# design.net
KiCad netlist of a schematic drawn in Altium Designer
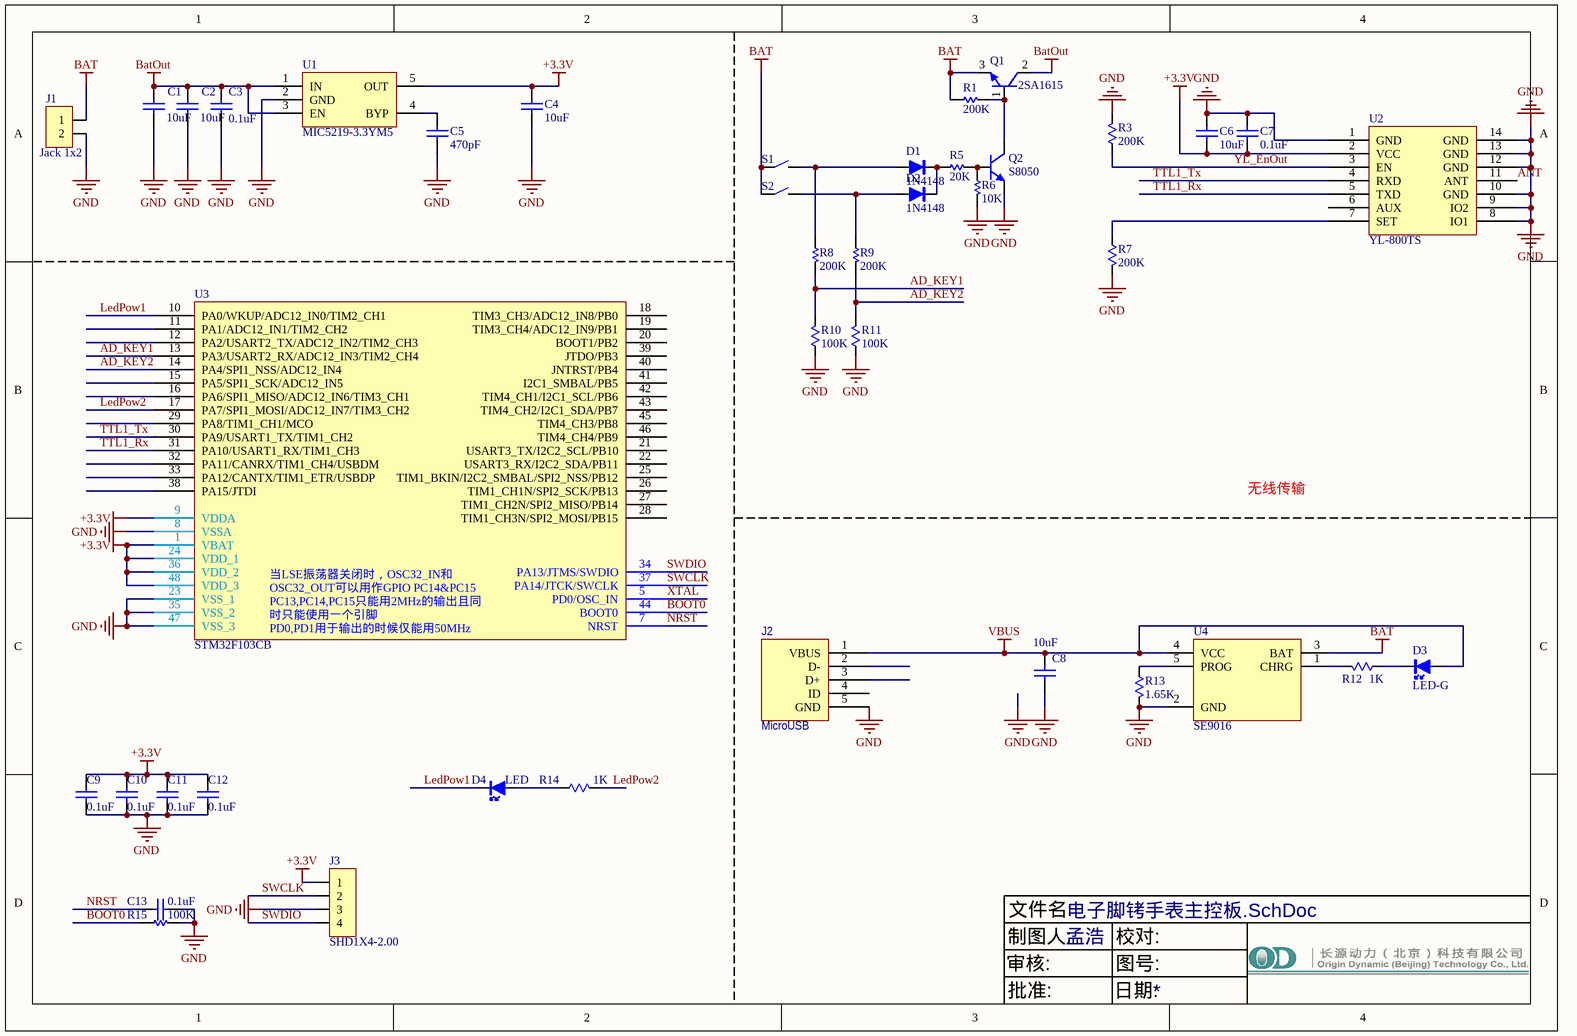
[diagram p0: 电子脚铐手表主控板.SchDoc]

(export (version "E")
  (design (tool "Eeschema 10.0.6"))
  (components
    (comp (ref "C1")
      (value "10uF")
      (footprint "C0603")
      (description "CAP")
      (fields (field (name "PUBLISHER") "Altium Limited"))
      (libsource (lib "Passive Components Class") (part "CAP"))
    )
    (comp (ref "C2")
      (value "10uF")
      (footprint "C0603")
      (description "CAP")
      (fields (field (name "PUBLISHER") "Altium Limited"))
      (libsource (lib "Passive Components Class") (part "CAP"))
    )
    (comp (ref "C3") (value "0.1uF") (footprint "C0603") (libsource (lib "RLCYDF") (part "Cap Semi")))
    (comp (ref "C4")
      (value "10uF")
      (footprint "C0603")
      (description "CAP")
      (fields (field (name "PUBLISHER") "Altium Limited"))
      (libsource (lib "Passive Components Class") (part "CAP"))
    )
    (comp (ref "C5")
      (value "470pF")
      (footprint "C0603")
      (description "CAP")
      (fields (field (name "PUBLISHER") "Altium Limited"))
      (libsource (lib "Passive Components Class") (part "CAP"))
    )
    (comp (ref "C6")
      (value "10uF")
      (footprint "C0603")
      (description "CAP")
      (fields (field (name "PUBLISHER") "Altium Limited"))
      (libsource (lib "Passive Components Class") (part "CAP"))
    )
    (comp (ref "C7")
      (value "0.1uF")
      (footprint "C0603")
      (description "CAP")
      (fields (field (name "PUBLISHER") "Altium Limited"))
      (libsource (lib "Passive Components Class") (part "CAP"))
    )
    (comp (ref "C8")
      (value "10uF")
      (footprint "C0603")
      (description "Capacitor")
      (fields (field (name "PUBLISHER") "Altium Limited"))
      (libsource (lib "Miscellaneous Devices") (part "Cap"))
    )
    (comp (ref "C9") (value "0.1uF") (footprint "C0603") (libsource (lib "RLCYDF") (part "Cap Semi")))
    (comp (ref "C10") (value "0.1uF") (footprint "C0603") (libsource (lib "RLCYDF") (part "Cap Semi")))
    (comp (ref "C11") (value "0.1uF") (footprint "C0603") (libsource (lib "RLCYDF") (part "Cap Semi")))
    (comp (ref "C12") (value "0.1uF") (footprint "C0603") (libsource (lib "RLCYDF") (part "Cap Semi")))
    (comp (ref "C13") (value "0.1uF") (footprint "C0603") (libsource (lib "RLCYDF") (part "Cap Semi")))
    (comp (ref "D1")
      (value "1N4148")
      (footprint "SOD-80-S")
      (description "Silicon Epitaxial Planar Diodes")
      (libsource (lib "Passive Components Class") (part "DIODE-SWITCHING"))
    )
    (comp (ref "D2")
      (value "1N4148")
      (footprint "SOD-80-S")
      (description "Silicon Epitaxial Planar Diodes")
      (libsource (lib "Passive Components Class") (part "DIODE-SWITCHING"))
    )
    (comp (ref "D3")
      (value "LED-G")
      (footprint "LED0603")
      (libsource (lib "Passive Components Class") (part "LED"))
    )
    (comp (ref "D4")
      (value "LED")
      (footprint "Led1206")
      (libsource (lib "Passive Components Class") (part "LED"))
    )
    (comp (ref "J1")
      (value "Jack 1x2")
      (footprint "Jk1*2-2.0")
      (description "插座")
      (libsource (lib "Connector") (part "Jack 1x2"))
    )
    (comp (ref "J2") (value "MicroUSB") (footprint "MICRO-USB") (libsource (lib "JLib") (part "MicroUSB")))
    (comp (ref "J3")
      (value "SHD1X4-2.00")
      (footprint "Jk1*4-2.0")
      (libsource (lib "Connector Class") (part "HEADER1X4"))
    )
    (comp (ref "Q1") (value "2SA1615") (footprint "TO-252") (libsource (lib "ArmArmor") (part "MJD122")))
    (comp (ref "Q2")
      (value "S8050")
      (footprint "SOT-23")
      (description "NPN triode, 0.5A Max")
      (libsource (lib "RLCYDF") (part "S8050"))
    )
    (comp (ref "R1") (value "200K") (footprint "R0603") (libsource (lib "RLCYDF") (part "Res")))
    (comp (ref "R3")
      (value "200K")
      (footprint "R0603")
      (description "Resistor")
      (fields (field (name "PUBLISHER") "Altium Limited"))
      (libsource (lib "Passive Components Class") (part "RES"))
    )
    (comp (ref "R5") (value "20K") (footprint "R0603") (libsource (lib "RLCYDF") (part "Res")))
    (comp (ref "R6") (value "10K") (footprint "R0603") (libsource (lib "RLCYDF") (part "Res")))
    (comp (ref "R7")
      (value "200K")
      (footprint "R0603")
      (description "Resistor")
      (fields (field (name "PUBLISHER") "Altium Limited"))
      (libsource (lib "Passive Components Class") (part "RES"))
    )
    (comp (ref "R8") (value "200K") (footprint "R0603") (libsource (lib "RLCYDF") (part "Res")))
    (comp (ref "R9") (value "200K") (footprint "R0603") (libsource (lib "RLCYDF") (part "Res")))
    (comp (ref "R10")
      (value "100K")
      (footprint "R0603")
      (description "Resistor")
      (fields (field (name "PUBLISHER") "Altium Limited"))
      (libsource (lib "Passive Components Class") (part "RES"))
    )
    (comp (ref "R11")
      (value "100K")
      (footprint "R0603")
      (description "Resistor")
      (fields (field (name "PUBLISHER") "Altium Limited"))
      (libsource (lib "Passive Components Class") (part "RES"))
    )
    (comp (ref "R12")
      (value "1K")
      (footprint "R0603")
      (description "Resistor")
      (fields (field (name "PUBLISHER") "Altium Limited"))
      (libsource (lib "UP-Robot") (part "Res"))
    )
    (comp (ref "R13")
      (value "1.65K")
      (footprint "R0603")
      (description "Resistor")
      (fields (field (name "PUBLISHER") "Altium Limited"))
      (libsource (lib "Temp") (part "Res"))
    )
    (comp (ref "R14")
      (value "1K")
      (footprint "R0603")
      (description "Resistor")
      (fields (field (name "PUBLISHER") "Altium Limited"))
      (libsource (lib "UP-Robot") (part "Res"))
    )
    (comp (ref "R15") (value "100K") (footprint "R0603") (libsource (lib "RLCYDF") (part "Res")))
    (comp (ref "S1") (value "Switch") (footprint "TS-1110U") (libsource (lib "Connector") (part "Sw")))
    (comp (ref "S2") (value "Switch") (footprint "SIDE_BUTTON") (libsource (lib "Connector") (part "Sw")))
    (comp (ref "U1")
      (value "MIC5219-3.3YM5")
      (footprint "SOT-23-5")
      (libsource (lib "Power") (part "MIC5205"))
    )
    (comp (ref "U2") (value "YL-800TS") (footprint "YL-800TS") (libsource (lib "Module") (part "YL-800TS")))
    (comp (ref "U3")
      (value "STM32F103CB")
      (footprint "LQFP48")
      (libsource (lib "stm32") (part "STM32F103Cx"))
    )
    (comp (ref "U4") (value "SE9016") (footprint "SOT-23-5") (libsource (lib "chip") (part "SE9016")))
  )
  (nets
    (net (code "1") (name "+3.3V") (class "Default")
      (node (ref "C10") (pin "1") (pinfunction "1_1") (pintype "passive"))
      (node (ref "C11") (pin "1") (pinfunction "1_1") (pintype "passive"))
      (node (ref "C12") (pin "1") (pinfunction "1_1") (pintype "passive"))
      (node (ref "C4") (pin "1") (pinfunction "1_1") (pintype "passive"))
      (node (ref "C6") (pin "1") (pinfunction "1_1") (pintype "passive"))
      (node (ref "C7") (pin "1") (pinfunction "1_1") (pintype "passive"))
      (node (ref "C9") (pin "1") (pinfunction "1_1") (pintype "passive"))
      (node (ref "J3") (pin "1") (pinfunction "1_1") (pintype "passive"))
      (node (ref "U1") (pin "5") (pinfunction "OUT_5") (pintype "passive"))
      (node (ref "U2") (pin "2") (pinfunction "VCC_2") (pintype "passive"))
      (node (ref "U3") (pin "1") (pinfunction "VBAT_1") (pintype "power_in"))
      (node (ref "U3") (pin "24") (pinfunction "VDD_1_24") (pintype "power_in"))
      (node (ref "U3") (pin "36") (pinfunction "VDD_2_36") (pintype "power_in"))
      (node (ref "U3") (pin "48") (pinfunction "VDD_3_48") (pintype "power_in"))
      (node (ref "U3") (pin "9") (pinfunction "VDDA_9") (pintype "power_in"))
    )
    (net (code "2") (name "/AD_KEY1") (class "Default")
      (node (ref "R10") (pin "2") (pinfunction "2_2") (pintype "passive"))
      (node (ref "R8") (pin "2") (pinfunction "2_2") (pintype "passive"))
      (node (ref "U3") (pin "13") (pinfunction "PA3/USART2_RX/ADC12_IN3/TIM2_CH4_13") (pintype "passive"))
    )
    (net (code "3") (name "/AD_KEY2") (class "Default")
      (node (ref "R11") (pin "2") (pinfunction "2_2") (pintype "passive"))
      (node (ref "R9") (pin "2") (pinfunction "2_2") (pintype "passive"))
      (node (ref "U3") (pin "14") (pinfunction "PA4/SPI1_NSS/ADC12_IN4_14") (pintype "passive"))
    )
    (net (code "4") (name "/ANT") (class "Default")
      (node (ref "U2") (pin "11") (pinfunction "ANT_11") (pintype "passive"))
    )
    (net (code "5") (name "/BOOT0") (class "Default")
      (node (ref "R15") (pin "1") (pinfunction "1_1") (pintype "passive"))
      (node (ref "U3") (pin "44") (pinfunction "BOOT0_44") (pintype "passive"))
    )
    (net (code "6") (name "/LedPow1") (class "Default")
      (node (ref "D4") (pin "2") (pinfunction "K_2") (pintype "passive"))
      (node (ref "U3") (pin "10") (pinfunction "PA0/WKUP/ADC12_IN0/TIM2_CH1_10") (pintype "passive"))
    )
    (net (code "7") (name "/LedPow2") (class "Default")
      (node (ref "R14") (pin "1") (pinfunction "1_1") (pintype "passive"))
      (node (ref "U3") (pin "17") (pinfunction "PA7/SPI1_MOSI/ADC12_IN7/TIM3_CH2_17") (pintype "passive"))
    )
    (net (code "8") (name "/NRST") (class "Default")
      (node (ref "C13") (pin "1") (pinfunction "1_1") (pintype "passive"))
      (node (ref "U3") (pin "7") (pinfunction "NRST_7") (pintype "passive"))
    )
    (net (code "9") (name "/SWCLK") (class "Default")
      (node (ref "J3") (pin "2") (pinfunction "2_2") (pintype "passive"))
      (node (ref "U3") (pin "37") (pinfunction "PA14/JTCK/SWCLK_37") (pintype "passive"))
    )
    (net (code "10") (name "/SWDIO") (class "Default")
      (node (ref "J3") (pin "4") (pinfunction "4_4") (pintype "passive"))
      (node (ref "U3") (pin "34") (pinfunction "PA13/JTMS/SWDIO_34") (pintype "passive"))
    )
    (net (code "11") (name "/TTL1_Rx") (class "Default")
      (node (ref "U2") (pin "5") (pinfunction "TXD_5") (pintype "passive"))
      (node (ref "U3") (pin "31") (pinfunction "PA10/USART1_RX/TIM1_CH3_31") (pintype "passive"))
    )
    (net (code "12") (name "/TTL1_Tx") (class "Default")
      (node (ref "U2") (pin "4") (pinfunction "RXD_4") (pintype "passive"))
      (node (ref "U3") (pin "30") (pinfunction "PA9/USART1_TX/TIM1_CH2_30") (pintype "passive"))
    )
    (net (code "13") (name "/XTAL") (class "Default")
      (node (ref "U3") (pin "5") (pinfunction "PD0/OSC_IN_5") (pintype "passive"))
    )
    (net (code "14") (name "/YL_EnOut") (class "Default")
      (node (ref "R3") (pin "1") (pinfunction "1_1") (pintype "passive"))
      (node (ref "U2") (pin "3") (pinfunction "EN_3") (pintype "passive"))
    )
    (net (code "15") (name "BAT") (class "Default")
      (node (ref "J1") (pin "1") (pinfunction "1_1") (pintype "passive"))
      (node (ref "Q1") (pin "3") (pinfunction "E_3") (pintype "passive"))
      (node (ref "R1") (pin "1") (pinfunction "1_1") (pintype "passive"))
      (node (ref "S1") (pin "1") (pinfunction "1_1") (pintype "passive"))
      (node (ref "S2") (pin "1") (pinfunction "1_1") (pintype "passive"))
      (node (ref "U4") (pin "3") (pinfunction "BAT_3") (pintype "passive"))
    )
    (net (code "16") (name "BatOut") (class "Default")
      (node (ref "C1") (pin "1") (pinfunction "1_1") (pintype "passive"))
      (node (ref "C2") (pin "1") (pinfunction "1_1") (pintype "passive"))
      (node (ref "C3") (pin "2") (pinfunction "2_2") (pintype "passive"))
      (node (ref "Q1") (pin "2") (pinfunction "C_2") (pintype "passive"))
      (node (ref "U1") (pin "1") (pinfunction "IN_1") (pintype "passive"))
      (node (ref "U1") (pin "3") (pinfunction "EN_3") (pintype "passive"))
    )
    (net (code "17") (name "GND") (class "Default")
      (node (ref "C1") (pin "2") (pinfunction "2_2") (pintype "passive"))
      (node (ref "C10") (pin "2") (pinfunction "2_2") (pintype "passive"))
      (node (ref "C11") (pin "2") (pinfunction "2_2") (pintype "passive"))
      (node (ref "C12") (pin "2") (pinfunction "2_2") (pintype "passive"))
      (node (ref "C13") (pin "2") (pinfunction "2_2") (pintype "passive"))
      (node (ref "C2") (pin "2") (pinfunction "2_2") (pintype "passive"))
      (node (ref "C3") (pin "1") (pinfunction "1_1") (pintype "passive"))
      (node (ref "C4") (pin "2") (pinfunction "2_2") (pintype "passive"))
      (node (ref "C5") (pin "2") (pinfunction "2_2") (pintype "passive"))
      (node (ref "C6") (pin "2") (pinfunction "2_2") (pintype "passive"))
      (node (ref "C7") (pin "2") (pinfunction "2_2") (pintype "passive"))
      (node (ref "C8") (pin "2") (pinfunction "2_2") (pintype "passive"))
      (node (ref "C9") (pin "2") (pinfunction "2_2") (pintype "passive"))
      (node (ref "J1") (pin "2") (pinfunction "2_2") (pintype "passive"))
      (node (ref "J2") (pin "5") (pinfunction "GND_5") (pintype "passive"))
      (node (ref "J3") (pin "3") (pinfunction "3_3") (pintype "passive"))
      (node (ref "Q2") (pin "2") (pinfunction "e_2") (pintype "passive"))
      (node (ref "R10") (pin "1") (pinfunction "1_1") (pintype "passive"))
      (node (ref "R11") (pin "1") (pinfunction "1_1") (pintype "passive"))
      (node (ref "R13") (pin "1") (pinfunction "1_1") (pintype "passive"))
      (node (ref "R15") (pin "2") (pinfunction "2_2") (pintype "passive"))
      (node (ref "R3") (pin "2") (pinfunction "2_2") (pintype "passive"))
      (node (ref "R6") (pin "2") (pinfunction "2_2") (pintype "passive"))
      (node (ref "R7") (pin "2") (pinfunction "2_2") (pintype "passive"))
      (node (ref "U1") (pin "2") (pinfunction "GND_2") (pintype "passive"))
      (node (ref "U2") (pin "1") (pinfunction "GND_1") (pintype "passive"))
      (node (ref "U2") (pin "10") (pinfunction "GND_10") (pintype "passive"))
      (node (ref "U2") (pin "12") (pinfunction "GND_12") (pintype "passive"))
      (node (ref "U2") (pin "13") (pinfunction "GND_13") (pintype "passive"))
      (node (ref "U2") (pin "14") (pinfunction "GND_14") (pintype "passive"))
      (node (ref "U2") (pin "8") (pinfunction "IO1_8") (pintype "passive"))
      (node (ref "U2") (pin "9") (pinfunction "IO2_9") (pintype "passive"))
      (node (ref "U3") (pin "23") (pinfunction "VSS_1_23") (pintype "power_in"))
      (node (ref "U3") (pin "35") (pinfunction "VSS_2_35") (pintype "power_in"))
      (node (ref "U3") (pin "47") (pinfunction "VSS_3_47") (pintype "power_in"))
      (node (ref "U3") (pin "8") (pinfunction "VSSA_8") (pintype "power_in"))
      (node (ref "U4") (pin "2") (pinfunction "GND_2") (pintype "passive"))
    )
    (net (code "18") (name "Net-(D1-A)") (class "Default")
      (node (ref "D1") (pin "1") (pinfunction "A_1") (pintype "passive"))
      (node (ref "R8") (pin "1") (pinfunction "1_1") (pintype "passive"))
      (node (ref "S1") (pin "2") (pinfunction "2_2") (pintype "passive"))
    )
    (net (code "19") (name "Net-(D1-K)") (class "Default")
      (node (ref "D1") (pin "2") (pinfunction "K_2") (pintype "passive"))
      (node (ref "D2") (pin "2") (pinfunction "K_2") (pintype "passive"))
      (node (ref "R5") (pin "1") (pinfunction "1_1") (pintype "passive"))
    )
    (net (code "20") (name "Net-(D2-A)") (class "Default")
      (node (ref "D2") (pin "1") (pinfunction "A_1") (pintype "passive"))
      (node (ref "R9") (pin "1") (pinfunction "1_1") (pintype "passive"))
      (node (ref "S2") (pin "2") (pinfunction "2_2") (pintype "passive"))
    )
    (net (code "21") (name "Net-(D3-K)") (class "Default")
      (node (ref "D3") (pin "2") (pinfunction "K_2") (pintype "passive"))
      (node (ref "R12") (pin "2") (pinfunction "2_2") (pintype "passive"))
    )
    (net (code "22") (name "Net-(D4-A)") (class "Default")
      (node (ref "D4") (pin "1") (pinfunction "A_1") (pintype "passive"))
      (node (ref "R14") (pin "2") (pinfunction "2_2") (pintype "passive"))
    )
    (net (code "23") (name "Net-(Q1-B)") (class "Default")
      (node (ref "Q1") (pin "1") (pinfunction "B_1") (pintype "passive"))
      (node (ref "Q2") (pin "3") (pinfunction "c_3") (pintype "passive"))
      (node (ref "R1") (pin "2") (pinfunction "2_2") (pintype "passive"))
    )
    (net (code "24") (name "Net-(Q2-b)") (class "Default")
      (node (ref "Q2") (pin "1") (pinfunction "b_1") (pintype "passive"))
      (node (ref "R5") (pin "2") (pinfunction "2_2") (pintype "passive"))
      (node (ref "R6") (pin "1") (pinfunction "1_1") (pintype "passive"))
    )
    (net (code "25") (name "Net-(U1-BYP)") (class "Default")
      (node (ref "C5") (pin "1") (pinfunction "1_1") (pintype "passive"))
      (node (ref "U1") (pin "4") (pinfunction "BYP_4") (pintype "passive"))
    )
    (net (code "26") (name "Net-(U2-SET)") (class "Default")
      (node (ref "R7") (pin "1") (pinfunction "1_1") (pintype "passive"))
      (node (ref "U2") (pin "7") (pinfunction "SET_7") (pintype "passive"))
    )
    (net (code "27") (name "Net-(U4-CHRG)") (class "Default")
      (node (ref "R12") (pin "1") (pinfunction "1_1") (pintype "passive"))
      (node (ref "U4") (pin "1") (pinfunction "CHRG_1") (pintype "passive"))
    )
    (net (code "28") (name "Net-(U4-PROG)") (class "Default")
      (node (ref "R13") (pin "2") (pinfunction "2_2") (pintype "passive"))
      (node (ref "U4") (pin "5") (pinfunction "PROG_5") (pintype "passive"))
    )
    (net (code "29") (name "VBUS") (class "Default")
      (node (ref "C8") (pin "1") (pinfunction "1_1") (pintype "passive"))
      (node (ref "D3") (pin "1") (pinfunction "A_1") (pintype "passive"))
      (node (ref "J2") (pin "1") (pinfunction "VBUS_1") (pintype "passive"))
      (node (ref "U4") (pin "4") (pinfunction "VCC_4") (pintype "passive"))
    )
    (net (code "30") (name "unconnected-(J2-D+-Pad3)") (class "Default")
      (node (ref "J2") (pin "3") (pinfunction "D+_3") (pintype "passive"))
    )
    (net (code "31") (name "unconnected-(J2-D--Pad2)") (class "Default")
      (node (ref "J2") (pin "2") (pinfunction "D-_2") (pintype "passive"))
    )
    (net (code "32") (name "unconnected-(J2-ID-Pad4)") (class "Default")
      (node (ref "J2") (pin "4") (pinfunction "ID_4") (pintype "passive"))
    )
    (net (code "33") (name "unconnected-(U2-AUX-Pad6)") (class "Default")
      (node (ref "U2") (pin "6") (pinfunction "AUX_6") (pintype "passive"))
    )
    (net (code "34") (name "unconnected-(U3-BOOT1{slash}PB2-Pad20)") (class "Default")
      (node (ref "U3") (pin "20") (pinfunction "BOOT1/PB2_20") (pintype "passive"))
    )
    (net (code "35") (name "unconnected-(U3-I2C1_SMBAL{slash}PB5-Pad41)") (class "Default")
      (node (ref "U3") (pin "41") (pinfunction "I2C1_SMBAL/PB5_41") (pintype "passive"))
    )
    (net (code "36") (name "unconnected-(U3-JNTRST{slash}PB4-Pad40)") (class "Default")
      (node (ref "U3") (pin "40") (pinfunction "JNTRST/PB4_40") (pintype "passive"))
    )
    (net (code "37") (name "unconnected-(U3-JTDO{slash}PB3-Pad39)") (class "Default")
      (node (ref "U3") (pin "39") (pinfunction "JTDO/PB3_39") (pintype "passive"))
    )
    (net (code "38") (name "unconnected-(U3-PA1{slash}ADC12_IN1{slash}TIM2_CH2-Pad11)") (class "Default")
      (node (ref "U3") (pin "11") (pinfunction "PA1/ADC12_IN1/TIM2_CH2_11") (pintype "passive"))
    )
    (net (code "39") (name "unconnected-(U3-PA2{slash}USART2_TX{slash}ADC12_IN2{slash}TIM2_CH3-Pad12)") (class "Default")
      (node (ref "U3") (pin "12") (pinfunction "PA2/USART2_TX/ADC12_IN2/TIM2_CH3_12") (pintype "passive"))
    )
    (net (code "40") (name "unconnected-(U3-PA5{slash}SPI1_SCK{slash}ADC12_IN5-Pad15)") (class "Default")
      (node (ref "U3") (pin "15") (pinfunction "PA5/SPI1_SCK/ADC12_IN5_15") (pintype "passive"))
    )
    (net (code "41") (name "unconnected-(U3-PA6{slash}SPI1_MISO{slash}ADC12_IN6{slash}TIM3_CH1-Pad16)") (class "Default")
      (node (ref "U3") (pin "16") (pinfunction "PA6/SPI1_MISO/ADC12_IN6/TIM3_CH1_16") (pintype "passive"))
    )
    (net (code "42") (name "unconnected-(U3-PA8{slash}TIM1_CH1{slash}MCO-Pad29)") (class "Default")
      (node (ref "U3") (pin "29") (pinfunction "PA8/TIM1_CH1/MCO_29") (pintype "passive"))
    )
    (net (code "43") (name "unconnected-(U3-PA11{slash}CANRX{slash}TIM1_CH4{slash}USBDM-Pad32)") (class "Default")
      (node (ref "U3") (pin "32") (pinfunction "PA11/CANRX/TIM1_CH4/USBDM_32") (pintype "passive"))
    )
    (net (code "44") (name "unconnected-(U3-PA12{slash}CANTX{slash}TIM1_ETR{slash}USBDP-Pad33)") (class "Default")
      (node (ref "U3") (pin "33") (pinfunction "PA12/CANTX/TIM1_ETR/USBDP_33") (pintype "passive"))
    )
    (net (code "45") (name "unconnected-(U3-PA15{slash}JTDI-Pad38)") (class "Default")
      (node (ref "U3") (pin "38") (pinfunction "PA15/JTDI_38") (pintype "passive"))
    )
    (net (code "46") (name "unconnected-(U3-PC13-TAMPER-RTC-Pad2)") (class "Default")
      (node (ref "U3") (pin "2") (pinfunction "PC13-TAMPER-RTC_2") (pintype "passive"))
    )
    (net (code "47") (name "unconnected-(U3-PC14-OSC32_IN-Pad3)") (class "Default")
      (node (ref "U3") (pin "3") (pinfunction "PC14-OSC32_IN_3") (pintype "passive"))
    )
    (net (code "48") (name "unconnected-(U3-PC15-OSC32_OUT-Pad4)") (class "Default")
      (node (ref "U3") (pin "4") (pinfunction "PC15-OSC32_OUT_4") (pintype "passive"))
    )
    (net (code "49") (name "unconnected-(U3-PD1{slash}OSC_OUT-Pad6)") (class "Default")
      (node (ref "U3") (pin "6") (pinfunction "PD1/OSC_OUT_6") (pintype "passive"))
    )
    (net (code "50") (name "unconnected-(U3-TIM1_BKIN{slash}I2C2_SMBAL{slash}SPI2_NSS{slash}PB12-Pad25)") (class "Default")
      (node (ref "U3") (pin "25") (pinfunction "TIM1_BKIN/I2C2_SMBAL/SPI2_NSS/PB12_25") (pintype "passive"))
    )
    (net (code "51") (name "unconnected-(U3-TIM1_CH1N{slash}SPI2_SCK{slash}PB13-Pad26)") (class "Default")
      (node (ref "U3") (pin "26") (pinfunction "TIM1_CH1N/SPI2_SCK/PB13_26") (pintype "passive"))
    )
    (net (code "52") (name "unconnected-(U3-TIM1_CH2N{slash}SPI2_MISO{slash}PB14-Pad27)") (class "Default")
      (node (ref "U3") (pin "27") (pinfunction "TIM1_CH2N/SPI2_MISO/PB14_27") (pintype "passive"))
    )
    (net (code "53") (name "unconnected-(U3-TIM1_CH3N{slash}SPI2_MOSI{slash}PB15-Pad28)") (class "Default")
      (node (ref "U3") (pin "28") (pinfunction "TIM1_CH3N/SPI2_MOSI/PB15_28") (pintype "passive"))
    )
    (net (code "54") (name "unconnected-(U3-TIM3_CH3{slash}ADC12_IN8{slash}PB0-Pad18)") (class "Default")
      (node (ref "U3") (pin "18") (pinfunction "TIM3_CH3/ADC12_IN8/PB0_18") (pintype "passive"))
    )
    (net (code "55") (name "unconnected-(U3-TIM3_CH4{slash}ADC12_IN9{slash}PB1-Pad19)") (class "Default")
      (node (ref "U3") (pin "19") (pinfunction "TIM3_CH4/ADC12_IN9/PB1_19") (pintype "passive"))
    )
    (net (code "56") (name "unconnected-(U3-TIM4_CH1{slash}I2C1_SCL{slash}PB6-Pad42)") (class "Default")
      (node (ref "U3") (pin "42") (pinfunction "TIM4_CH1/I2C1_SCL/PB6_42") (pintype "passive"))
    )
    (net (code "57") (name "unconnected-(U3-TIM4_CH2{slash}I2C1_SDA{slash}PB7-Pad43)") (class "Default")
      (node (ref "U3") (pin "43") (pinfunction "TIM4_CH2/I2C1_SDA/PB7_43") (pintype "passive"))
    )
    (net (code "58") (name "unconnected-(U3-TIM4_CH3{slash}PB8-Pad45)") (class "Default")
      (node (ref "U3") (pin "45") (pinfunction "TIM4_CH3/PB8_45") (pintype "passive"))
    )
    (net (code "59") (name "unconnected-(U3-TIM4_CH4{slash}PB9-Pad46)") (class "Default")
      (node (ref "U3") (pin "46") (pinfunction "TIM4_CH4/PB9_46") (pintype "passive"))
    )
    (net (code "60") (name "unconnected-(U3-USART3_RX{slash}I2C2_SDA{slash}PB11-Pad22)") (class "Default")
      (node (ref "U3") (pin "22") (pinfunction "USART3_RX/I2C2_SDA/PB11_22") (pintype "passive"))
    )
    (net (code "61") (name "unconnected-(U3-USART3_TX{slash}I2C2_SCL{slash}PB10-Pad21)") (class "Default")
      (node (ref "U3") (pin "21") (pinfunction "USART3_TX/I2C2_SCL/PB10_21") (pintype "passive"))
    )
  )
)
